# Power_Management.net
KiCad netlist of a schematic drawn in Altium Designer
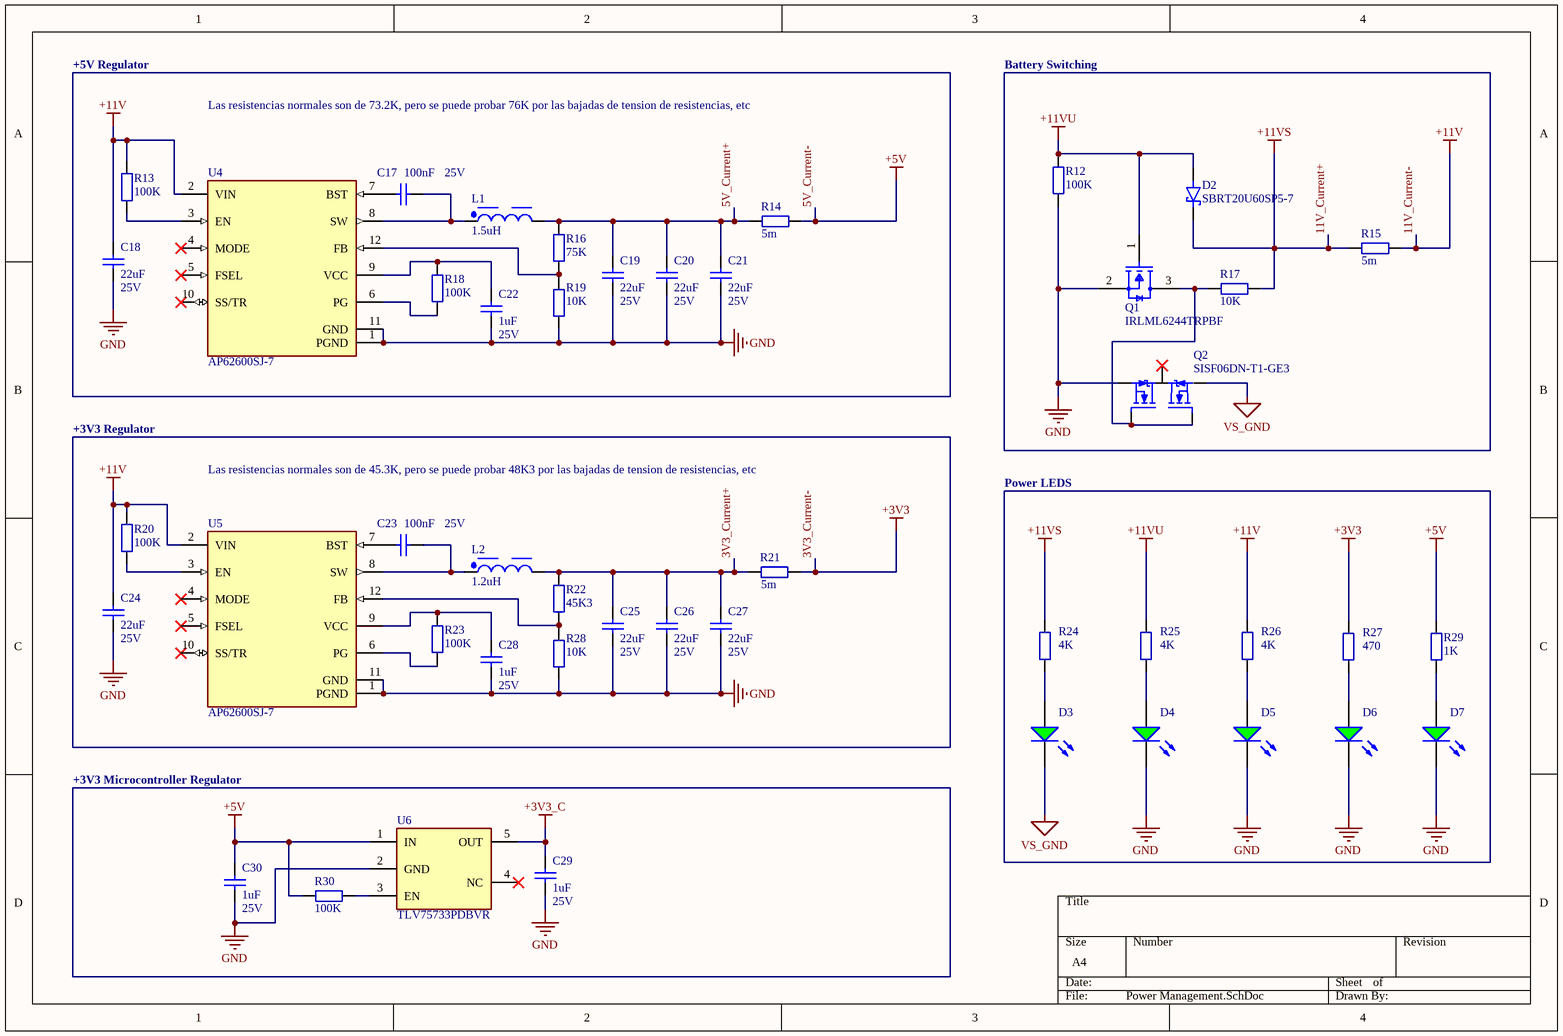
[diagram p0: Power Management.SchDoc]

(export (version "E")
  (design (tool "Eeschema 10.0.6"))
  (components
    (comp (ref "C17")
      (value "100nF")
      (footprint "MY_0603")
      (description "Capacitor, 100nF, 0603, 25V")
      (fields
        (field (name "VOLTAGE") "25V")
        (field (name "MANUFACTURER") "Wurth Elektronik")
        (field (name "MANUFACTURER PART NUMBER") "885012206071")
      )
      (libsource (lib "LEEM UPM") (part "Cap ceramic"))
    )
    (comp (ref "C18")
      (value "22uF")
      (footprint "MY_0805")
      (description "Capacitor, 22uF, 0805, 25V")
      (fields
        (field (name "MANUFACTURER") "Samsung")
        (field (name "MANUFACTURER PART NUMBER") "CL21A226MAYNNNE")
        (field (name "VOLTAGE") "25V")
      )
      (libsource (lib "LEEM UPM") (part "Cap ceramic"))
    )
    (comp (ref "C19")
      (value "22uF")
      (footprint "MY_0805")
      (description "Capacitor, 22uF, 0805, 25V")
      (fields
        (field (name "MANUFACTURER") "Samsung")
        (field (name "MANUFACTURER PART NUMBER") "CL21A226MAYNNNE")
        (field (name "VOLTAGE") "25V")
      )
      (libsource (lib "LEEM UPM") (part "Cap ceramic"))
    )
    (comp (ref "C20")
      (value "22uF")
      (footprint "MY_0805")
      (description "Capacitor, 22uF, 0805, 25V")
      (fields
        (field (name "MANUFACTURER") "Samsung")
        (field (name "MANUFACTURER PART NUMBER") "CL21A226MAYNNNE")
        (field (name "VOLTAGE") "25V")
      )
      (libsource (lib "LEEM UPM") (part "Cap ceramic"))
    )
    (comp (ref "C21")
      (value "22uF")
      (footprint "MY_0805")
      (description "Capacitor, 22uF, 0805, 25V")
      (fields
        (field (name "MANUFACTURER") "Samsung")
        (field (name "MANUFACTURER PART NUMBER") "CL21A226MAYNNNE")
        (field (name "VOLTAGE") "25V")
      )
      (libsource (lib "LEEM UPM") (part "Cap ceramic"))
    )
    (comp (ref "C22")
      (value "1uF")
      (footprint "MY_0603")
      (description "Capacitor, 1uF, 0603, 25V")
      (fields
        (field (name "VOLTE") "25V")
        (field (name "MANUFACTURER") "Wurth Elektronik")
        (field (name "MANUFACTURER PART NUMBER") "885012206052")
      )
      (libsource (lib "LEEM UPM") (part "Cap ceramic"))
    )
    (comp (ref "C23")
      (value "100nF")
      (footprint "MY_0603")
      (description "Capacitor, 100nF, 0603, 25V")
      (fields
        (field (name "VOLTAGE") "25V")
        (field (name "MANUFACTURER") "Wurth Elektronik")
        (field (name "MANUFACTURER PART NUMBER") "885012206071")
      )
      (libsource (lib "LEEM UPM") (part "Cap ceramic"))
    )
    (comp (ref "C24")
      (value "22uF")
      (footprint "MY_0805")
      (description "Capacitor, 22uF, 0805, 25V")
      (fields
        (field (name "MANUFACTURER") "Samsung")
        (field (name "MANUFACTURER PART NUMBER") "CL21A226MAYNNNE")
        (field (name "VOLTAGE") "25V")
      )
      (libsource (lib "LEEM UPM") (part "Cap ceramic"))
    )
    (comp (ref "C25")
      (value "22uF")
      (footprint "MY_0805")
      (description "None polar capacitor")
      (fields
        (field (name "MANUFACTURER") "Samsung")
        (field (name "MANUFACTURER PART NUMBER") "CL21A226MAYNNNE")
        (field (name "VOLTAGE") "25V")
      )
      (libsource (lib "LEEM UPM") (part "Cap ceramic"))
    )
    (comp (ref "C26")
      (value "22uF")
      (footprint "MY_0805")
      (description "None polar capacitor")
      (fields
        (field (name "MANUFACTURER") "Samsung")
        (field (name "MANUFACTURER PART NUMBER") "CL21A226MAYNNNE")
        (field (name "VOLTAGE") "25V")
      )
      (libsource (lib "LEEM UPM") (part "Cap ceramic"))
    )
    (comp (ref "C27")
      (value "22uF")
      (footprint "MY_0805")
      (description "None polar capacitor")
      (fields
        (field (name "MANUFACTURER") "Samsung")
        (field (name "MANUFACTURER PART NUMBER") "CL21A226MAYNNNE")
        (field (name "VOLTAGE") "25V")
      )
      (libsource (lib "LEEM UPM") (part "Cap ceramic"))
    )
    (comp (ref "C28")
      (value "1uF")
      (footprint "MY_0603")
      (description "Capacitor, 1uF, 0603, 25V")
      (fields
        (field (name "VOLTE") "25V")
        (field (name "MANUFACTURER") "Wurth Elektronik")
        (field (name "MANUFACTURER PART NUMBER") "885012206052")
      )
      (libsource (lib "LEEM UPM") (part "Cap ceramic"))
    )
    (comp (ref "C29")
      (value "1uF")
      (footprint "MY_0603")
      (description "Capacitor, 1uF, 0603, 25V")
      (fields
        (field (name "VOLTE") "25V")
        (field (name "MANUFACTURER") "Wurth Elektronik")
        (field (name "MANUFACTURER PART NUMBER") "885012206052")
      )
      (libsource (lib "LEEM UPM") (part "Cap ceramic"))
    )
    (comp (ref "C30")
      (value "1uF")
      (footprint "MY_0603")
      (description "Capacitor, 1uF, 0603, 25V")
      (fields
        (field (name "VOLTE") "25V")
        (field (name "MANUFACTURER") "Wurth Elektronik")
        (field (name "MANUFACTURER PART NUMBER") "885012206052")
      )
      (libsource (lib "LEEM UPM") (part "Cap ceramic"))
    )
    (comp (ref "D2")
      (value "SBRT20U60SP5-7")
      (footprint "SBRT20U60SP5-7-Footprint-1")
      (description "Rectifier Diode, 1 Phase, 1 Element, 20A, 60V V(RRM), Silicon")
      (fields (field (name "MANUFACTURER") "Diodes Incorporated"))
      (libsource (lib "LEEM UPM") (part "SBRT20U60SP5"))
    )
    (comp (ref "D3")
      (value "~")
      (footprint "WL-SMCW_0805_150080xx75000")
      (description "LED, 0805, Green")
      (fields
        (field (name "MANUFACTURER") "Wurth Elektronik")
        (field (name "MANUFACTURER PART NUMBER") "150080GS75000")
      )
      (libsource (lib "Altium Content Vault") (part "LED_Green_2A-1K"))
    )
    (comp (ref "D4")
      (value "~")
      (footprint "WL-SMCW_0805_150080xx75000")
      (description "LED, 0805, Green")
      (fields
        (field (name "MANUFACTURER") "Wurth Elektronik")
        (field (name "MANUFACTURER PART NUMBER") "150080GS75000")
      )
      (libsource (lib "Altium Content Vault") (part "LED_Green_2A-1K"))
    )
    (comp (ref "D5")
      (value "~")
      (footprint "WL-SMCW_0805_150080xx75000")
      (description "LED, 0805, Green")
      (fields
        (field (name "MANUFACTURER") "Wurth Elektronik")
        (field (name "MANUFACTURER PART NUMBER") "150080GS75000")
      )
      (libsource (lib "Altium Content Vault") (part "LED_Green_2A-1K"))
    )
    (comp (ref "D6")
      (value "~")
      (footprint "WL-SMCW_0805_150080xx75000")
      (description "LED, 0805, Green")
      (fields
        (field (name "MANUFACTURER") "Wurth Elektronik")
        (field (name "MANUFACTURER PART NUMBER") "150080GS75000")
      )
      (libsource (lib "Altium Content Vault") (part "LED_Green_2A-1K"))
    )
    (comp (ref "D7")
      (value "~")
      (footprint "WL-SMCW_0805_150080xx75000")
      (description "LED, 0805, Green")
      (fields
        (field (name "MANUFACTURER") "Wurth Elektronik")
        (field (name "MANUFACTURER PART NUMBER") "150080GS75000")
      )
      (libsource (lib "Altium Content Vault") (part "LED_Green_2A-1K"))
    )
    (comp (ref "L1")
      (value "1.5uH")
      (footprint "WE-MAPI_4020")
      (description "74438356015 Fixed Ind 1.5UH 5.8A 19 Mohm SMD")
      (fields
        (field (name "MANUFACTURER") "Wurth Elektronik")
        (field (name "MANUFACTURER PART NUMBER") "74438356015")
      )
      (libsource (lib "Altium Content Vault") (part "Inductor - 2"))
    )
    (comp (ref "L2")
      (value "1.2uH")
      (footprint "WE-MAPI_4020")
      (description "FIXED IND 1.2UH 5.8A 18 MOHM SMD")
      (fields
        (field (name "MANUFACTURER") "Wurth Elektronik")
        (field (name "MANUFACTURER PART NUMBER") "74438356012")
      )
      (libsource (lib "Altium Content Vault") (part "Inductor - 2"))
    )
    (comp (ref "Q1")
      (value "IRLML6244TRPBF")
      (footprint "FP-Micro3-IPC_C")
      (libsource (lib "LEEM UPM") (part "3b9c635fedb024a5347a57b145af9cc"))
    )
    (comp (ref "Q2")
      (value "SISF06DN-T1-GE3")
      (footprint "SISF06DN-T1-GE3-Footprint-1")
      (libsource (lib "LEEM UPM") (part "SISF06DN"))
    )
    (comp (ref "R12")
      (value "100K")
      (footprint "R0603-0.45")
      (description "Resistor, 100K, 0603, 0.1W")
      (fields (field (name "MANUFACTURER") "Wurth") (field (name "MANUFACTURER PART NUMBER") "560112116004"))
      (libsource (lib "IFS_Altium") (part "R"))
    )
    (comp (ref "R13")
      (value "100K")
      (footprint "R0603-0.45")
      (description "Resistor, 100K, 0603, 0.1W")
      (fields (field (name "MANUFACTURER") "Wurth") (field (name "MANUFACTURER PART NUMBER") "560112116004"))
      (libsource (lib "IFS_Altium") (part "R"))
    )
    (comp (ref "R14")
      (value "5m")
      (footprint "R0612")
      (description "Resistor, 5m, 0612, 2W")
      (fields
        (field (name "MANUFACTURER") "Vishay")
        (field (name "MANUFACTURER PART NUMBER") "WFCP06125L000FE66")
      )
      (libsource (lib "LEEM UPM") (part "RK73H2ALTD1004F"))
    )
    (comp (ref "R15")
      (value "5m")
      (footprint "R0612")
      (description "Resistor, 5m, 0612, 2W")
      (fields
        (field (name "MANUFACTURER") "Vishay")
        (field (name "MANUFACTURER PART NUMBER") "WFCP06125L000FE66")
      )
      (libsource (lib "LEEM UPM") (part "RK73H2ALTD1004F"))
    )
    (comp (ref "R16")
      (value "75K")
      (footprint "R0603-0.45")
      (description "Resistor, 75K, 0603, 0.1W")
      (fields (field (name "MANUFACTURER") "Wurth") (field (name "MANUFACTURER PART NUMBER") "560112110261"))
      (libsource (lib "IFS_Altium") (part "R"))
    )
    (comp (ref "R17")
      (value "10K")
      (footprint "R0603-0.45")
      (description "Resistor, 10K, 0603, 0.1W")
      (fields (field (name "MANUFACTURER") "Wurth") (field (name "MANUFACTURER PART NUMBER") "560112116005"))
      (libsource (lib "IFS_Altium") (part "R"))
    )
    (comp (ref "R18")
      (value "100K")
      (footprint "R0603-0.45")
      (description "Resistor, 100K, 0603, 0.1W")
      (fields (field (name "MANUFACTURER") "Wurth") (field (name "MANUFACTURER PART NUMBER") "560112116004"))
      (libsource (lib "IFS_Altium") (part "R"))
    )
    (comp (ref "R19")
      (value "10K")
      (footprint "R0603-0.45")
      (description "Resistor, 10K, 0603, 0.1W")
      (fields (field (name "MANUFACTURER") "Wurth") (field (name "MANUFACTURER PART NUMBER") "560112116005"))
      (libsource (lib "IFS_Altium") (part "R"))
    )
    (comp (ref "R20")
      (value "100K")
      (footprint "R0603-0.45")
      (description "Resistor, 100K, 0603, 0.1W")
      (fields (field (name "MANUFACTURER") "Wurth") (field (name "MANUFACTURER PART NUMBER") "560112116004"))
      (libsource (lib "IFS_Altium") (part "R"))
    )
    (comp (ref "R21")
      (value "5m")
      (footprint "R0612")
      (description "Resistor, 5m, 0612, 2W")
      (fields
        (field (name "MANUFACTURER") "Vishay")
        (field (name "MANUFACTURER PART NUMBER") "WFCP06125L000FE66")
      )
      (libsource (lib "LEEM UPM") (part "RK73H2ALTD1004F"))
    )
    (comp (ref "R22")
      (value "45K3")
      (footprint "R0603-0.45")
      (description "Resistor, 45.3kK, 0603, 0.1W")
      (fields (field (name "MANUFACTURER") "Wurth") (field (name "MANUFACTURER PART NUMBER") "560112110243"))
      (libsource (lib "IFS_Altium") (part "R"))
    )
    (comp (ref "R23")
      (value "100K")
      (footprint "R0603-0.45")
      (description "Resistor, 100K, 0603, 0.1W")
      (fields (field (name "MANUFACTURER") "Wurth") (field (name "MANUFACTURER PART NUMBER") "560112116004"))
      (libsource (lib "IFS_Altium") (part "R"))
    )
    (comp (ref "R24")
      (value "4K")
      (footprint "R0603-0.45")
      (description "Resistor, 4K, 0603, 0.1W")
      (fields (field (name "MANUFACTURER") "Wurth") (field (name "MANUFACTURER PART NUMBER") "560112116093"))
      (libsource (lib "LEEM UPM") (part "RK73H2ALTD1004F"))
    )
    (comp (ref "R25")
      (value "4K")
      (footprint "R0603-0.45")
      (description "Resistor, 4K, 0603, 0.1W")
      (fields (field (name "MANUFACTURER") "Wurth") (field (name "MANUFACTURER PART NUMBER") "560112116093"))
      (libsource (lib "LEEM UPM") (part "RK73H2ALTD1004F"))
    )
    (comp (ref "R26")
      (value "4K")
      (footprint "R0603-0.45")
      (description "Resistor, 4K, 0603, 0.1W")
      (fields (field (name "MANUFACTURER") "Wurth") (field (name "MANUFACTURER PART NUMBER") "560112116093"))
      (libsource (lib "LEEM UPM") (part "RK73H2ALTD1004F"))
    )
    (comp (ref "R27")
      (value "470")
      (footprint "R0603-0.45")
      (description "Resistor, 470K, 0603, 0.1W")
      (fields (field (name "MANUFACTURER") "Wurth") (field (name "MANUFACTURER PART NUMBER") "560112116067"))
      (libsource (lib "LEEM UPM") (part "RK73H2ALTD1004F"))
    )
    (comp (ref "R28")
      (value "10K")
      (footprint "R0603-0.45")
      (description "Resistor, 10K, 0603, 0.1W")
      (fields (field (name "MANUFACTURER") "Wurth") (field (name "MANUFACTURER PART NUMBER") "560112116005"))
      (libsource (lib "IFS_Altium") (part "R"))
    )
    (comp (ref "R29")
      (value "1K")
      (footprint "R0603-0.45")
      (description "Resistor, 1kK, 0603, 0.1W")
      (fields (field (name "MANUFACTURER") "Wurth") (field (name "MANUFACTURER PART NUMBER") "560112116014"))
      (libsource (lib "LEEM UPM") (part "RK73H2ALTD1004F"))
    )
    (comp (ref "R30")
      (value "100K")
      (footprint "R0603-0.45")
      (description "Resistor, 75K, 0603, 0.1W")
      (fields (field (name "MANUFACTURER") "Wurth") (field (name "MANUFACTURER PART NUMBER") "560112116004"))
      (libsource (lib "IFS_Altium") (part "R"))
    )
    (comp (ref "U4")
      (value "AP62600SJ-7")
      (footprint "FP-V-QFN2030-12_Type_A-MFG")
      (description "Switching Regulator, 1200kHz Switching Freq-Max")
      (fields (field (name "MANUFACTURER") "Diodes Incorporated"))
      (libsource (lib "LEEM UPM") (part "03c86ce2703f4b33b3045e94f7be521"))
    )
    (comp (ref "U5")
      (value "AP62600SJ-7")
      (footprint "FP-V-QFN2030-12_Type_A-MFG")
      (description "Switching Regulator, 1200kHz Switching Freq-Max")
      (fields (field (name "MANUFACTURER") "Diodes Incorporated"))
      (libsource (lib "LEEM UPM") (part "03c86ce2703f4b33b3045e94f7be521"))
    )
    (comp (ref "U6")
      (value "TLV75733PDBVR")
      (footprint "SOT95P280X145-5N")
      (description "LDO Voltage Regulators 1A Low-IQ Small-Size Low-Dropout (LDO) Regulator 5-SOT-23 -40 to 125")
      (fields (field (name "MANUFACTURER") "Texas Instruments"))
      (libsource (lib "LEEM UPM") (part "TLV75733PDBVR"))
    )
  )
  (nets
    (net (code "1") (name "+3V3") (class "Default")
      (node (ref "R21") (pin "2") (pinfunction "2_2") (pintype "passive"))
      (node (ref "R27") (pin "2") (pinfunction "2_2") (pintype "passive"))
    )
    (net (code "2") (name "+3V3_C") (class "Default")
      (node (ref "C29") (pin "2") (pinfunction "2_2") (pintype "passive"))
      (node (ref "U6") (pin "5") (pinfunction "OUT_5") (pintype "passive"))
    )
    (net (code "3") (name "+5V") (class "Default")
      (node (ref "C30") (pin "2") (pinfunction "2_2") (pintype "passive"))
      (node (ref "R14") (pin "2") (pinfunction "2_2") (pintype "passive"))
      (node (ref "R29") (pin "2") (pinfunction "2_2") (pintype "passive"))
      (node (ref "R30") (pin "1") (pinfunction "1_1") (pintype "passive"))
      (node (ref "U6") (pin "1") (pinfunction "IN_1") (pintype "power_in"))
    )
    (net (code "4") (name "+11V") (class "Default")
      (node (ref "C18") (pin "1") (pinfunction "1_1") (pintype "passive"))
      (node (ref "C24") (pin "1") (pinfunction "1_1") (pintype "passive"))
      (node (ref "R13") (pin "1") (pinfunction "1_1") (pintype "passive"))
      (node (ref "R15") (pin "2") (pinfunction "2_2") (pintype "passive"))
      (node (ref "R20") (pin "1") (pinfunction "1_1") (pintype "passive"))
      (node (ref "R26") (pin "2") (pinfunction "2_2") (pintype "passive"))
      (node (ref "U4") (pin "2") (pinfunction "VIN_2") (pintype "power_in"))
      (node (ref "U5") (pin "2") (pinfunction "VIN_2") (pintype "power_in"))
    )
    (net (code "5") (name "+11VS") (class "Default")
      (node (ref "D2") (pin "2") (pinfunction "2_2") (pintype "passive"))
      (node (ref "R15") (pin "1") (pinfunction "1_1") (pintype "passive"))
      (node (ref "R17") (pin "2") (pinfunction "2_2") (pintype "passive"))
      (node (ref "R24") (pin "2") (pinfunction "2_2") (pintype "passive"))
    )
    (net (code "6") (name "+11VU") (class "Default")
      (node (ref "D2") (pin "1") (pinfunction "1_1") (pintype "passive"))
      (node (ref "Q1") (pin "1") (pinfunction "G_1") (pintype "passive"))
      (node (ref "R12") (pin "1") (pinfunction "1_1") (pintype "passive"))
      (node (ref "R25") (pin "2") (pinfunction "2_2") (pintype "passive"))
    )
    (net (code "7") (name "/3V3_Current+") (class "Default")
      (node (ref "C25") (pin "1") (pinfunction "1_1") (pintype "passive"))
      (node (ref "C26") (pin "1") (pinfunction "1_1") (pintype "passive"))
      (node (ref "C27") (pin "1") (pinfunction "1_1") (pintype "passive"))
      (node (ref "L2") (pin "2") (pinfunction "2_2") (pintype "passive"))
      (node (ref "R21") (pin "1") (pinfunction "1_1") (pintype "passive"))
      (node (ref "R22") (pin "1") (pinfunction "1_1") (pintype "passive"))
    )
    (net (code "8") (name "/5V_Current+") (class "Default")
      (node (ref "C19") (pin "1") (pinfunction "1_1") (pintype "passive"))
      (node (ref "C20") (pin "1") (pinfunction "1_1") (pintype "passive"))
      (node (ref "C21") (pin "1") (pinfunction "1_1") (pintype "passive"))
      (node (ref "L1") (pin "2") (pinfunction "2_2") (pintype "passive"))
      (node (ref "R14") (pin "1") (pinfunction "1_1") (pintype "passive"))
      (node (ref "R16") (pin "1") (pinfunction "1_1") (pintype "passive"))
    )
    (net (code "9") (name "GND") (class "Default")
      (node (ref "C18") (pin "2") (pinfunction "2_2") (pintype "passive"))
      (node (ref "C19") (pin "2") (pinfunction "2_2") (pintype "passive"))
      (node (ref "C20") (pin "2") (pinfunction "2_2") (pintype "passive"))
      (node (ref "C21") (pin "2") (pinfunction "2_2") (pintype "passive"))
      (node (ref "C22") (pin "1") (pinfunction "1_1") (pintype "passive"))
      (node (ref "C24") (pin "2") (pinfunction "2_2") (pintype "passive"))
      (node (ref "C25") (pin "2") (pinfunction "2_2") (pintype "passive"))
      (node (ref "C26") (pin "2") (pinfunction "2_2") (pintype "passive"))
      (node (ref "C27") (pin "2") (pinfunction "2_2") (pintype "passive"))
      (node (ref "C28") (pin "1") (pinfunction "1_1") (pintype "passive"))
      (node (ref "C29") (pin "1") (pinfunction "1_1") (pintype "passive"))
      (node (ref "C30") (pin "1") (pinfunction "1_1") (pintype "passive"))
      (node (ref "D4") (pin "1") (pinfunction "K_1") (pintype "passive"))
      (node (ref "D5") (pin "1") (pinfunction "K_1") (pintype "passive"))
      (node (ref "D6") (pin "1") (pinfunction "K_1") (pintype "passive"))
      (node (ref "D7") (pin "1") (pinfunction "K_1") (pintype "passive"))
      (node (ref "Q1") (pin "2") (pinfunction "S_2") (pintype "passive"))
      (node (ref "Q2") (pin "4") (pinfunction "S1_4") (pintype "passive"))
      (node (ref "R12") (pin "2") (pinfunction "2_2") (pintype "passive"))
      (node (ref "R19") (pin "2") (pinfunction "2_2") (pintype "passive"))
      (node (ref "R28") (pin "2") (pinfunction "2_2") (pintype "passive"))
      (node (ref "U4") (pin "1") (pinfunction "PGND_1") (pintype "power_in"))
      (node (ref "U4") (pin "11") (pinfunction "GND_11") (pintype "power_in"))
      (node (ref "U5") (pin "1") (pinfunction "PGND_1") (pintype "power_in"))
      (node (ref "U5") (pin "11") (pinfunction "GND_11") (pintype "power_in"))
      (node (ref "U6") (pin "2") (pinfunction "GND_2") (pintype "passive"))
    )
    (net (code "10") (name "Net-(D3-A)") (class "Default")
      (node (ref "D3") (pin "2") (pinfunction "A_2") (pintype "passive"))
      (node (ref "R24") (pin "1") (pinfunction "1_1") (pintype "passive"))
    )
    (net (code "11") (name "Net-(D4-A)") (class "Default")
      (node (ref "D4") (pin "2") (pinfunction "A_2") (pintype "passive"))
      (node (ref "R25") (pin "1") (pinfunction "1_1") (pintype "passive"))
    )
    (net (code "12") (name "Net-(D5-A)") (class "Default")
      (node (ref "D5") (pin "2") (pinfunction "A_2") (pintype "passive"))
      (node (ref "R26") (pin "1") (pinfunction "1_1") (pintype "passive"))
    )
    (net (code "13") (name "Net-(D6-A)") (class "Default")
      (node (ref "D6") (pin "2") (pinfunction "A_2") (pintype "passive"))
      (node (ref "R27") (pin "1") (pinfunction "1_1") (pintype "passive"))
    )
    (net (code "14") (name "Net-(D7-A)") (class "Default")
      (node (ref "D7") (pin "2") (pinfunction "A_2") (pintype "passive"))
      (node (ref "R29") (pin "1") (pinfunction "1_1") (pintype "passive"))
    )
    (net (code "15") (name "Net-(Q1-D)") (class "Default")
      (node (ref "Q1") (pin "3") (pinfunction "D_3") (pintype "passive"))
      (node (ref "Q2") (pin "1") (pinfunction "G1_1") (pintype "passive"))
      (node (ref "Q2") (pin "3") (pinfunction "G2_3") (pintype "passive"))
      (node (ref "R17") (pin "1") (pinfunction "1_1") (pintype "passive"))
    )
    (net (code "16") (name "Net-(U4-BST)") (class "Default")
      (node (ref "C17") (pin "2") (pinfunction "2_2") (pintype "passive"))
      (node (ref "U4") (pin "7") (pinfunction "BST_7") (pintype "input"))
    )
    (net (code "17") (name "Net-(U4-EN)") (class "Default")
      (node (ref "R13") (pin "2") (pinfunction "2_2") (pintype "passive"))
      (node (ref "U4") (pin "3") (pinfunction "EN_3") (pintype "input"))
    )
    (net (code "18") (name "Net-(U4-FB)") (class "Default")
      (node (ref "R16") (pin "2") (pinfunction "2_2") (pintype "passive"))
      (node (ref "R19") (pin "1") (pinfunction "1_1") (pintype "passive"))
      (node (ref "U4") (pin "12") (pinfunction "FB_12") (pintype "input"))
    )
    (net (code "19") (name "Net-(U4-PG)") (class "Default")
      (node (ref "R18") (pin "2") (pinfunction "2_2") (pintype "passive"))
      (node (ref "U4") (pin "6") (pinfunction "PG_6") (pintype "open_collector"))
    )
    (net (code "20") (name "Net-(U4-SW)") (class "Default")
      (node (ref "C17") (pin "1") (pinfunction "1_1") (pintype "passive"))
      (node (ref "L1") (pin "1") (pinfunction "1_1") (pintype "passive"))
      (node (ref "U4") (pin "8") (pinfunction "SW_8") (pintype "output"))
    )
    (net (code "21") (name "Net-(U4-VCC)") (class "Default")
      (node (ref "C22") (pin "2") (pinfunction "2_2") (pintype "passive"))
      (node (ref "R18") (pin "1") (pinfunction "1_1") (pintype "passive"))
      (node (ref "U4") (pin "9") (pinfunction "VCC_9") (pintype "power_in"))
    )
    (net (code "22") (name "Net-(U5-BST)") (class "Default")
      (node (ref "C23") (pin "2") (pinfunction "2_2") (pintype "passive"))
      (node (ref "U5") (pin "7") (pinfunction "BST_7") (pintype "input"))
    )
    (net (code "23") (name "Net-(U5-EN)") (class "Default")
      (node (ref "R20") (pin "2") (pinfunction "2_2") (pintype "passive"))
      (node (ref "U5") (pin "3") (pinfunction "EN_3") (pintype "input"))
    )
    (net (code "24") (name "Net-(U5-FB)") (class "Default")
      (node (ref "R22") (pin "2") (pinfunction "2_2") (pintype "passive"))
      (node (ref "R28") (pin "1") (pinfunction "1_1") (pintype "passive"))
      (node (ref "U5") (pin "12") (pinfunction "FB_12") (pintype "input"))
    )
    (net (code "25") (name "Net-(U5-PG)") (class "Default")
      (node (ref "R23") (pin "2") (pinfunction "2_2") (pintype "passive"))
      (node (ref "U5") (pin "6") (pinfunction "PG_6") (pintype "open_collector"))
    )
    (net (code "26") (name "Net-(U5-SW)") (class "Default")
      (node (ref "C23") (pin "1") (pinfunction "1_1") (pintype "passive"))
      (node (ref "L2") (pin "1") (pinfunction "1_1") (pintype "passive"))
      (node (ref "U5") (pin "8") (pinfunction "SW_8") (pintype "output"))
    )
    (net (code "27") (name "Net-(U5-VCC)") (class "Default")
      (node (ref "C28") (pin "2") (pinfunction "2_2") (pintype "passive"))
      (node (ref "R23") (pin "1") (pinfunction "1_1") (pintype "passive"))
      (node (ref "U5") (pin "9") (pinfunction "VCC_9") (pintype "power_in"))
    )
    (net (code "28") (name "Net-(U6-EN)") (class "Default")
      (node (ref "R30") (pin "2") (pinfunction "2_2") (pintype "passive"))
      (node (ref "U6") (pin "3") (pinfunction "EN_3") (pintype "passive"))
    )
    (net (code "29") (name "VS_GND") (class "Default")
      (node (ref "D3") (pin "1") (pinfunction "K_1") (pintype "passive"))
      (node (ref "Q2") (pin "5") (pinfunction "S2_5") (pintype "passive"))
    )
    (net (code "30") (name "unconnected-(Q2-D-Pad2)") (class "Default")
      (node (ref "Q2") (pin "2") (pinfunction "D_2") (pintype "passive+no_connect"))
    )
    (net (code "31") (name "unconnected-(U4-FSEL-Pad5)") (class "Default")
      (node (ref "U4") (pin "5") (pinfunction "FSEL_5") (pintype "input+no_connect"))
    )
    (net (code "32") (name "unconnected-(U4-MODE-Pad4)") (class "Default")
      (node (ref "U4") (pin "4") (pinfunction "MODE_4") (pintype "input+no_connect"))
    )
    (net (code "33") (name "unconnected-(U4-SS{slash}TR-Pad10)") (class "Default")
      (node (ref "U4") (pin "10") (pinfunction "SS/TR_10") (pintype "bidirectional+no_connect"))
    )
    (net (code "34") (name "unconnected-(U5-FSEL-Pad5)") (class "Default")
      (node (ref "U5") (pin "5") (pinfunction "FSEL_5") (pintype "input+no_connect"))
    )
    (net (code "35") (name "unconnected-(U5-MODE-Pad4)") (class "Default")
      (node (ref "U5") (pin "4") (pinfunction "MODE_4") (pintype "input+no_connect"))
    )
    (net (code "36") (name "unconnected-(U5-SS{slash}TR-Pad10)") (class "Default")
      (node (ref "U5") (pin "10") (pinfunction "SS/TR_10") (pintype "bidirectional+no_connect"))
    )
    (net (code "37") (name "unconnected-(U6-NC-Pad4)") (class "Default")
      (node (ref "U6") (pin "4") (pinfunction "NC_4") (pintype "passive+no_connect"))
    )
  )
)
